# led_strip_controller.net
KiCad netlist of a schematic drawn in EAGLE
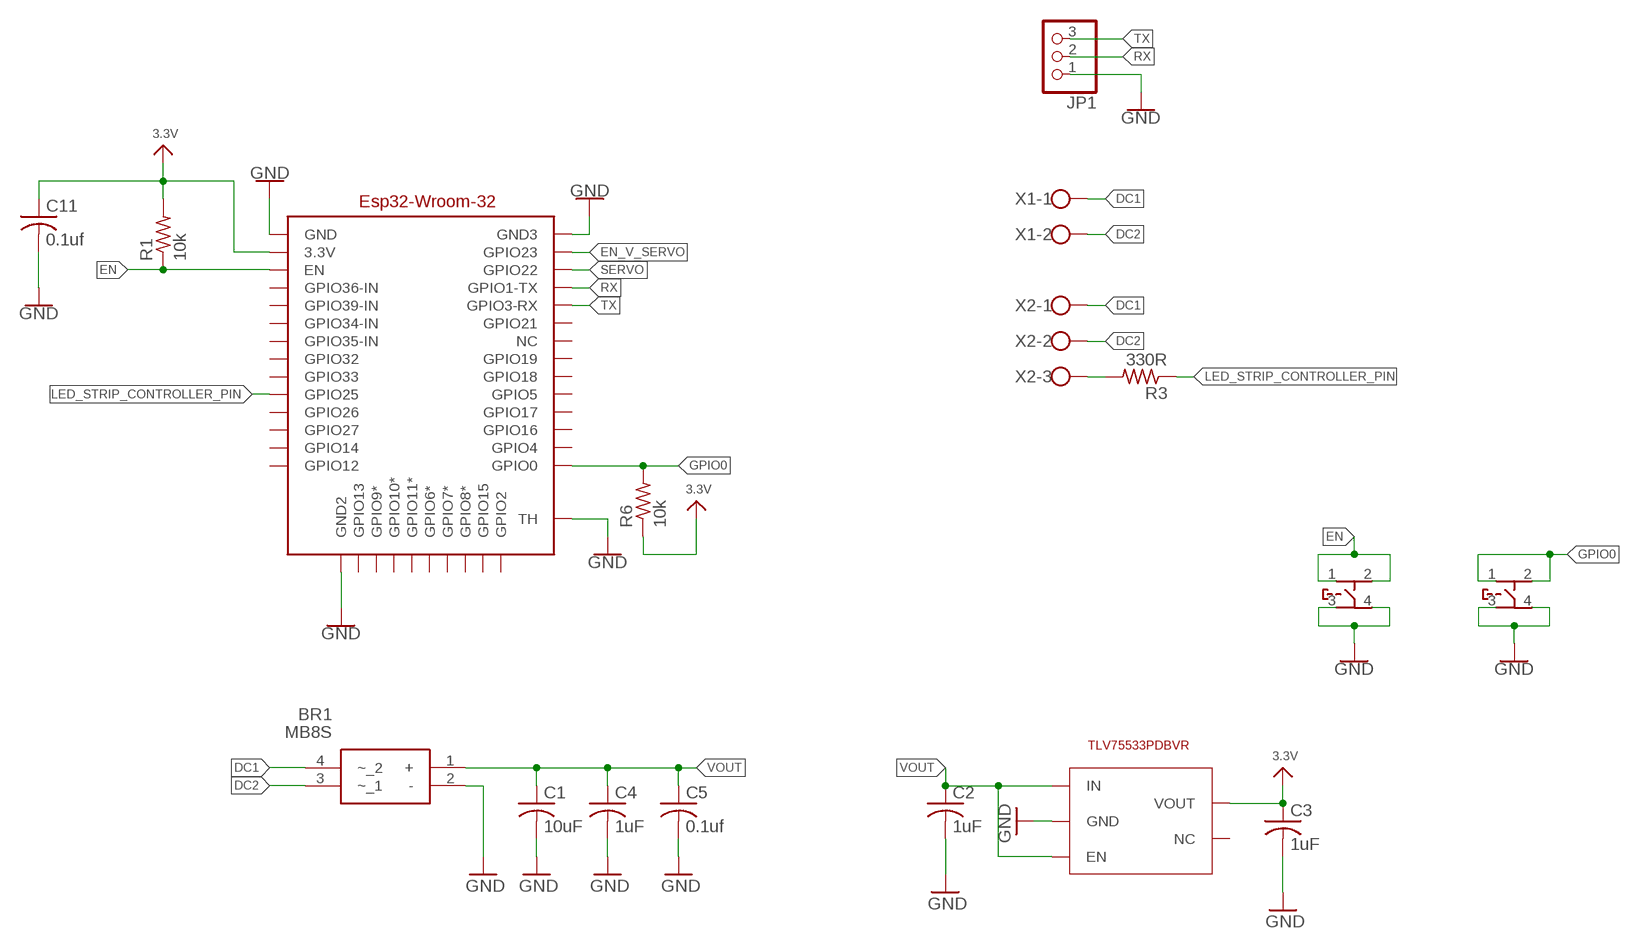
[diagram p0: schematic, sheet 1]

(export (version "E")
  (design (tool "Eeschema 10.0.6"))
  (components
    (comp (ref "BR1")
      (value "MB8S")
      (footprint "eagle-import:SOP245P670X290-4N")
      (fields (field (name "MOUSER_PART_NUMBER") "512-MB8S"))
      (libsource (lib "eagle-import") (part "MB8S"))
    )
    (comp (ref "C1")
      (value "10uF")
      (footprint "eagle-import:C1206")
      (libsource (lib "eagle-import") (part "C-USC1206"))
    )
    (comp (ref "C2")
      (value "1uF")
      (footprint "eagle-import:C0603")
      (libsource (lib "eagle-import") (part "rcl_334_C-USC0603"))
    )
    (comp (ref "C3")
      (value "1uF")
      (footprint "eagle-import:C0603")
      (libsource (lib "eagle-import") (part "rcl_334_C-USC0603"))
    )
    (comp (ref "C4")
      (value "1uF")
      (footprint "eagle-import:C0603")
      (libsource (lib "eagle-import") (part "rcl_334_C-USC0603"))
    )
    (comp (ref "C5")
      (value "0.1uf")
      (footprint "eagle-import:C0603")
      (libsource (lib "eagle-import") (part "rcl_334_C-USC0603"))
    )
    (comp (ref "C11")
      (value "0.1uf")
      (footprint "eagle-import:C0603")
      (libsource (lib "eagle-import") (part "rcl_334_C-USC0603"))
    )
    (comp (ref "JP1")
      (value "PINHD-1X3")
      (footprint "eagle-import:1X03")
      (libsource (lib "eagle-import") (part "PINHD-1X3"))
    )
    (comp (ref "R1")
      (value "10k")
      (footprint "eagle-import:R0603")
      (libsource (lib "eagle-import") (part "R-US_R0603"))
    )
    (comp (ref "R3")
      (value "330R")
      (footprint "eagle-import:R0603")
      (libsource (lib "eagle-import") (part "rcl_334_R-US_R0603"))
    )
    (comp (ref "R6")
      (value "10k")
      (footprint "eagle-import:R0603")
      (libsource (lib "eagle-import") (part "R-US_R0603"))
    )
    (comp (ref "U$1")
      (value "ESP32-WROM-32")
      (footprint "eagle-import:ESP-32FOOTPRINT")
      (libsource (lib "eagle-import") (part "ESP32-WROM-32"))
    )
    (comp (ref "U$29")
      (value "TLV75533PDBVR")
      (footprint "eagle-import:SOT-23-5")
      (libsource (lib "eagle-import") (part "TLV75533PDBVR"))
    )
    (comp (ref "U$33")
      (value "XUNPU")
      (footprint "eagle-import:TS-1089S")
      (libsource (lib "eagle-import") (part "XUNPU"))
    )
    (comp (ref "U$34")
      (value "XUNPU")
      (footprint "eagle-import:TS-1089S")
      (libsource (lib "eagle-import") (part "XUNPU"))
    )
    (comp (ref "X1")
      (value "W237-102")
      (footprint "eagle-import:W237-102")
      (fields (field (name "MPN") "237-102"))
      (libsource (lib "eagle-import") (part "W237-102"))
    )
    (comp (ref "X2")
      (value "W237-103")
      (footprint "eagle-import:W237-103")
      (fields (field (name "MPN") "237-103"))
      (libsource (lib "eagle-import") (part "W237-103"))
    )
  )
  (nets
    (net (code "1") (name "3.3V") (class "Default")
      (node (ref "C11") (pin "1") (pinfunction "1_1") (pintype "passive"))
      (node (ref "C3") (pin "1") (pinfunction "1_1") (pintype "passive"))
      (node (ref "R1") (pin "2") (pinfunction "2_2") (pintype "passive"))
      (node (ref "R6") (pin "1") (pinfunction "1_1") (pintype "passive"))
      (node (ref "U$1") (pin "3.3V") (pinfunction "3.3V_3.3V") (pintype "bidirectional"))
      (node (ref "U$29") (pin "VOUT") (pinfunction "VOUT_VOUT") (pintype "bidirectional"))
    )
    (net (code "2") (name "DC1") (class "Default")
      (node (ref "BR1") (pin "4") (pinfunction "~{_2}_4") (pintype "bidirectional"))
      (node (ref "X1") (pin "1") (pinfunction "KL_1") (pintype "passive"))
      (node (ref "X2") (pin "1") (pinfunction "KL_1") (pintype "passive"))
    )
    (net (code "3") (name "DC2") (class "Default")
      (node (ref "BR1") (pin "3") (pinfunction "~{_1}_3") (pintype "bidirectional"))
      (node (ref "X1") (pin "2") (pinfunction "KL_2") (pintype "passive"))
      (node (ref "X2") (pin "2") (pinfunction "KL_2") (pintype "passive"))
    )
    (net (code "4") (name "EN") (class "Default")
      (node (ref "R1") (pin "1") (pinfunction "1_1") (pintype "passive"))
      (node (ref "U$1") (pin "EN") (pinfunction "EN_EN") (pintype "bidirectional"))
      (node (ref "U$33") (pin "1") (pinfunction "1_1") (pintype "bidirectional"))
      (node (ref "U$33") (pin "2") (pinfunction "2_2") (pintype "bidirectional"))
    )
    (net (code "5") (name "EN_V_SERVO") (class "Default")
      (node (ref "U$1") (pin "GPIO23") (pinfunction "GPIO23_GPIO23") (pintype "bidirectional"))
    )
    (net (code "6") (name "GND") (class "Default")
      (node (ref "BR1") (pin "2") (pinfunction "-_2") (pintype "bidirectional"))
      (node (ref "C1") (pin "2") (pinfunction "2_2") (pintype "passive"))
      (node (ref "C11") (pin "2") (pinfunction "2_2") (pintype "passive"))
      (node (ref "C2") (pin "2") (pinfunction "2_2") (pintype "passive"))
      (node (ref "C3") (pin "2") (pinfunction "2_2") (pintype "passive"))
      (node (ref "C4") (pin "2") (pinfunction "2_2") (pintype "passive"))
      (node (ref "C5") (pin "2") (pinfunction "2_2") (pintype "passive"))
      (node (ref "JP1") (pin "1") (pinfunction "1_1") (pintype "passive"))
      (node (ref "U$1") (pin "GND") (pinfunction "GND_GND") (pintype "bidirectional"))
      (node (ref "U$1") (pin "GND2") (pinfunction "GND2_GND2") (pintype "bidirectional"))
      (node (ref "U$1") (pin "GND3") (pinfunction "GND3_GND3") (pintype "bidirectional"))
      (node (ref "U$1") (pin "TH") (pinfunction "TH_TH") (pintype "bidirectional"))
      (node (ref "U$29") (pin "GND") (pinfunction "GND_GND") (pintype "bidirectional"))
      (node (ref "U$33") (pin "3") (pinfunction "3_3") (pintype "bidirectional"))
      (node (ref "U$33") (pin "4") (pinfunction "4_4") (pintype "bidirectional"))
      (node (ref "U$34") (pin "3") (pinfunction "3_3") (pintype "bidirectional"))
      (node (ref "U$34") (pin "4") (pinfunction "4_4") (pintype "bidirectional"))
    )
    (net (code "7") (name "GPIO0") (class "Default")
      (node (ref "R6") (pin "2") (pinfunction "2_2") (pintype "passive"))
      (node (ref "U$1") (pin "GPIO0") (pinfunction "GPIO0_GPIO0") (pintype "bidirectional"))
      (node (ref "U$34") (pin "1") (pinfunction "1_1") (pintype "bidirectional"))
      (node (ref "U$34") (pin "2") (pinfunction "2_2") (pintype "bidirectional"))
    )
    (net (code "8") (name "LED_STRIP_CONTROLLER_PIN") (class "Default")
      (node (ref "R3") (pin "1") (pinfunction "1_1") (pintype "passive"))
      (node (ref "U$1") (pin "GPIO25") (pinfunction "GPIO25_GPIO25") (pintype "bidirectional"))
    )
    (net (code "9") (name "Net-(X2C-KL)") (class "Default")
      (node (ref "R3") (pin "2") (pinfunction "2_2") (pintype "passive"))
      (node (ref "X2") (pin "3") (pinfunction "KL_3") (pintype "passive"))
    )
    (net (code "10") (name "RX") (class "Default")
      (node (ref "JP1") (pin "2") (pinfunction "2_2") (pintype "passive"))
      (node (ref "U$1") (pin "GPIO1") (pinfunction "GPIO1-TX_GPIO1") (pintype "bidirectional"))
    )
    (net (code "11") (name "SERVO") (class "Default")
      (node (ref "U$1") (pin "GPO22") (pinfunction "GPIO22_GPO22") (pintype "bidirectional"))
    )
    (net (code "12") (name "TX") (class "Default")
      (node (ref "JP1") (pin "3") (pinfunction "3_3") (pintype "passive"))
      (node (ref "U$1") (pin "GPIO3") (pinfunction "GPIO3-RX_GPIO3") (pintype "bidirectional"))
    )
    (net (code "13") (name "VOUT") (class "Default")
      (node (ref "BR1") (pin "1") (pinfunction "+_1") (pintype "bidirectional"))
      (node (ref "C1") (pin "1") (pinfunction "1_1") (pintype "passive"))
      (node (ref "C2") (pin "1") (pinfunction "1_1") (pintype "passive"))
      (node (ref "C4") (pin "1") (pinfunction "1_1") (pintype "passive"))
      (node (ref "C5") (pin "1") (pinfunction "1_1") (pintype "passive"))
      (node (ref "U$29") (pin "EN") (pinfunction "EN_EN") (pintype "bidirectional"))
      (node (ref "U$29") (pin "IN") (pinfunction "IN_IN") (pintype "bidirectional"))
    )
    (net (code "14") (name "unconnected-(U$1-GPIO6*-PadGPIO6)") (class "Default")
      (node (ref "U$1") (pin "GPIO6") (pinfunction "GPIO6*_GPIO6") (pintype "bidirectional"))
    )
    (net (code "15") (name "unconnected-(U$1-GPIO7*-PadGPIO7)") (class "Default")
      (node (ref "U$1") (pin "GPIO7") (pinfunction "GPIO7*_GPIO7") (pintype "bidirectional"))
    )
    (net (code "16") (name "unconnected-(U$1-GPIO8*-PadGPIO8)") (class "Default")
      (node (ref "U$1") (pin "GPIO8") (pinfunction "GPIO8*_GPIO8") (pintype "bidirectional"))
    )
    (net (code "17") (name "unconnected-(U$1-GPIO9*-PadGPIO9)") (class "Default")
      (node (ref "U$1") (pin "GPIO9") (pinfunction "GPIO9*_GPIO9") (pintype "bidirectional"))
    )
    (net (code "18") (name "unconnected-(U$1-GPIO10*-PadGPIO10)") (class "Default")
      (node (ref "U$1") (pin "GPIO10") (pinfunction "GPIO10*_GPIO10") (pintype "bidirectional"))
    )
    (net (code "19") (name "unconnected-(U$1-GPIO11*-PadGPIO11)") (class "Default")
      (node (ref "U$1") (pin "GPIO11") (pinfunction "GPIO11*_GPIO11") (pintype "bidirectional"))
    )
    (net (code "20") (name "unconnected-(U$1-GPIO34-IN-PadGPIO34)") (class "Default")
      (node (ref "U$1") (pin "GPIO34") (pinfunction "GPIO34-IN_GPIO34") (pintype "bidirectional"))
    )
    (net (code "21") (name "unconnected-(U$1-GPIO35-IN-PadGPIO35)") (class "Default")
      (node (ref "U$1") (pin "GPIO35") (pinfunction "GPIO35-IN_GPIO35") (pintype "bidirectional"))
    )
    (net (code "22") (name "unconnected-(U$1-GPIO36-IN-PadGPIO36)") (class "Default")
      (node (ref "U$1") (pin "GPIO36") (pinfunction "GPIO36-IN_GPIO36") (pintype "bidirectional"))
    )
    (net (code "23") (name "unconnected-(U$1-GPIO39-IN-PadGPIO39)") (class "Default")
      (node (ref "U$1") (pin "GPIO39") (pinfunction "GPIO39-IN_GPIO39") (pintype "bidirectional"))
    )
    (net (code "24") (name "unconnected-(U$1-PadGPIO2)") (class "Default")
      (node (ref "U$1") (pin "GPIO2") (pinfunction "GPIO2_GPIO2") (pintype "bidirectional"))
    )
    (net (code "25") (name "unconnected-(U$1-PadGPIO4)") (class "Default")
      (node (ref "U$1") (pin "GPIO4") (pinfunction "GPIO4_GPIO4") (pintype "bidirectional"))
    )
    (net (code "26") (name "unconnected-(U$1-PadGPIO5)") (class "Default")
      (node (ref "U$1") (pin "GPIO5") (pinfunction "GPIO5_GPIO5") (pintype "bidirectional"))
    )
    (net (code "27") (name "unconnected-(U$1-PadGPIO12)") (class "Default")
      (node (ref "U$1") (pin "GPIO12") (pinfunction "GPIO12_GPIO12") (pintype "bidirectional"))
    )
    (net (code "28") (name "unconnected-(U$1-PadGPIO13)") (class "Default")
      (node (ref "U$1") (pin "GPIO13") (pinfunction "GPIO13_GPIO13") (pintype "bidirectional"))
    )
    (net (code "29") (name "unconnected-(U$1-PadGPIO14)") (class "Default")
      (node (ref "U$1") (pin "GPIO14") (pinfunction "GPIO14_GPIO14") (pintype "bidirectional"))
    )
    (net (code "30") (name "unconnected-(U$1-PadGPIO15)") (class "Default")
      (node (ref "U$1") (pin "GPIO15") (pinfunction "GPIO15_GPIO15") (pintype "bidirectional"))
    )
    (net (code "31") (name "unconnected-(U$1-PadGPIO16)") (class "Default")
      (node (ref "U$1") (pin "GPIO16") (pinfunction "GPIO16_GPIO16") (pintype "bidirectional"))
    )
    (net (code "32") (name "unconnected-(U$1-PadGPIO17)") (class "Default")
      (node (ref "U$1") (pin "GPIO17") (pinfunction "GPIO17_GPIO17") (pintype "bidirectional"))
    )
    (net (code "33") (name "unconnected-(U$1-PadGPIO18)") (class "Default")
      (node (ref "U$1") (pin "GPIO18") (pinfunction "GPIO18_GPIO18") (pintype "bidirectional"))
    )
    (net (code "34") (name "unconnected-(U$1-PadGPIO19)") (class "Default")
      (node (ref "U$1") (pin "GPIO19") (pinfunction "GPIO19_GPIO19") (pintype "bidirectional"))
    )
    (net (code "35") (name "unconnected-(U$1-PadGPIO21)") (class "Default")
      (node (ref "U$1") (pin "GPIO21") (pinfunction "GPIO21_GPIO21") (pintype "bidirectional"))
    )
    (net (code "36") (name "unconnected-(U$1-PadGPIO26)") (class "Default")
      (node (ref "U$1") (pin "GPIO26") (pinfunction "GPIO26_GPIO26") (pintype "bidirectional"))
    )
    (net (code "37") (name "unconnected-(U$1-PadGPIO27)") (class "Default")
      (node (ref "U$1") (pin "GPIO27") (pinfunction "GPIO27_GPIO27") (pintype "bidirectional"))
    )
    (net (code "38") (name "unconnected-(U$1-PadGPIO32)") (class "Default")
      (node (ref "U$1") (pin "GPIO32") (pinfunction "GPIO32_GPIO32") (pintype "bidirectional"))
    )
    (net (code "39") (name "unconnected-(U$1-PadGPIO33)") (class "Default")
      (node (ref "U$1") (pin "GPIO33") (pinfunction "GPIO33_GPIO33") (pintype "bidirectional"))
    )
    (net (code "40") (name "unconnected-(U$1-PadNC)") (class "Default")
      (node (ref "U$1") (pin "NC") (pinfunction "NC_NC") (pintype "bidirectional"))
    )
    (net (code "41") (name "unconnected-(U$29-PadNC)") (class "Default")
      (node (ref "U$29") (pin "NC") (pinfunction "NC_NC") (pintype "bidirectional"))
    )
  )
)
